# microcontroller.net
KiCad netlist of a schematic drawn in Altium Designer
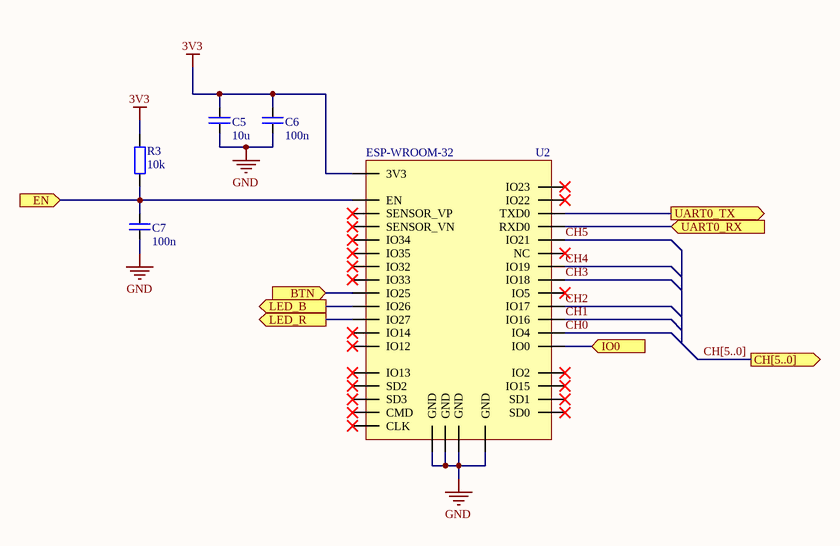
[diagram p0: microcontroller.SchDoc]

(export (version "E")
  (design (tool "Eeschema 10.0.6"))
  (components
    (comp (ref "C5")
      (value "10u")
      (footprint "capacitor_smd_0805")
      (description "TAIYO YUDEN TMK212BBJ106MGHT")
      (libsource (lib "generic") (part "Capacitor - non-polarised"))
    )
    (comp (ref "C6")
      (value "100n")
      (footprint "capacitor_smd_0603")
      (description "Vishay GA0603Y104KXAAC31G")
      (libsource (lib "generic") (part "Capacitor - non-polarised"))
    )
    (comp (ref "C7")
      (value "100n")
      (footprint "capacitor_smd_0603")
      (description "Vishay GA0603Y104KXAAC31G")
      (libsource (lib "generic") (part "Capacitor - non-polarised"))
    )
    (comp (ref "R3")
      (value "10k")
      (footprint "resisitor_smd_0603")
      (description "Vishay CRCW060310K0FKEI")
      (libsource (lib "generic") (part "Resistor"))
    )
    (comp (ref "U2")
      (value "ESP-WROOM-32")
      (footprint "ESP-WROOM-32_no_silk")
      (description "Espressif ESP-WROOM-32")
      (libsource (lib "integrated_circuits") (part "ESP-WROOM-32"))
    )
  )
  (nets
    (net (code "1") (name "/BTN") (class "Default")
      (node (ref "U2") (pin "10") (pinfunction "IO25_10") (pintype "passive"))
    )
    (net (code "2") (name "/CH0") (class "Default")
      (node (ref "U2") (pin "26") (pinfunction "IO4_26") (pintype "passive"))
    )
    (net (code "3") (name "/CH1") (class "Default")
      (node (ref "U2") (pin "27") (pinfunction "IO16_27") (pintype "passive"))
    )
    (net (code "4") (name "/CH2") (class "Default")
      (node (ref "U2") (pin "28") (pinfunction "IO17_28") (pintype "passive"))
    )
    (net (code "5") (name "/CH3") (class "Default")
      (node (ref "U2") (pin "30") (pinfunction "IO18_30") (pintype "passive"))
    )
    (net (code "6") (name "/CH4") (class "Default")
      (node (ref "U2") (pin "31") (pinfunction "IO19_31") (pintype "passive"))
    )
    (net (code "7") (name "/CH5") (class "Default")
      (node (ref "U2") (pin "33") (pinfunction "IO21_33") (pintype "passive"))
    )
    (net (code "9") (name "/EN") (class "Default")
      (node (ref "C7") (pin "1") (pintype "passive"))
      (node (ref "R3") (pin "2") (pintype "passive"))
      (node (ref "U2") (pin "3") (pinfunction "EN_3") (pintype "passive"))
    )
    (net (code "10") (name "/IO0") (class "Default")
      (node (ref "U2") (pin "25") (pinfunction "IO0_25") (pintype "passive"))
    )
    (net (code "11") (name "/LED_B") (class "Default")
      (node (ref "U2") (pin "11") (pinfunction "IO26_11") (pintype "passive"))
    )
    (net (code "12") (name "/LED_R") (class "Default")
      (node (ref "U2") (pin "12") (pinfunction "IO27_12") (pintype "passive"))
    )
    (net (code "13") (name "/UART0_RX") (class "Default")
      (node (ref "U2") (pin "34") (pinfunction "RXD0_34") (pintype "passive"))
    )
    (net (code "14") (name "/UART0_TX") (class "Default")
      (node (ref "U2") (pin "35") (pinfunction "TXD0_35") (pintype "passive"))
    )
    (net (code "15") (name "3V3") (class "Default")
      (node (ref "C5") (pin "1") (pintype "passive"))
      (node (ref "C6") (pin "1") (pintype "passive"))
      (node (ref "R3") (pin "1") (pintype "passive"))
      (node (ref "U2") (pin "2") (pinfunction "3V3_2") (pintype "passive"))
    )
    (net (code "16") (name "GND") (class "Default")
      (node (ref "C5") (pin "2") (pintype "passive"))
      (node (ref "C6") (pin "2") (pintype "passive"))
      (node (ref "C7") (pin "2") (pintype "passive"))
      (node (ref "U2") (pin "1") (pinfunction "GND_1") (pintype "passive"))
      (node (ref "U2") (pin "15") (pinfunction "GND_15") (pintype "passive"))
      (node (ref "U2") (pin "38") (pinfunction "GND_38") (pintype "passive"))
      (node (ref "U2") (pin "39") (pinfunction "GND_39") (pintype "passive"))
    )
    (net (code "17") (name "unconnected-(U2-CLK-Pad20)") (class "Default")
      (node (ref "U2") (pin "20") (pinfunction "CLK_20") (pintype "passive+no_connect"))
    )
    (net (code "18") (name "unconnected-(U2-CMD-Pad19)") (class "Default")
      (node (ref "U2") (pin "19") (pinfunction "CMD_19") (pintype "passive+no_connect"))
    )
    (net (code "19") (name "unconnected-(U2-IO2-Pad24)") (class "Default")
      (node (ref "U2") (pin "24") (pinfunction "IO2_24") (pintype "passive+no_connect"))
    )
    (net (code "20") (name "unconnected-(U2-IO5-Pad29)") (class "Default")
      (node (ref "U2") (pin "29") (pinfunction "IO5_29") (pintype "passive+no_connect"))
    )
    (net (code "21") (name "unconnected-(U2-IO12-Pad14)") (class "Default")
      (node (ref "U2") (pin "14") (pinfunction "IO12_14") (pintype "passive+no_connect"))
    )
    (net (code "22") (name "unconnected-(U2-IO13-Pad16)") (class "Default")
      (node (ref "U2") (pin "16") (pinfunction "IO13_16") (pintype "passive+no_connect"))
    )
    (net (code "23") (name "unconnected-(U2-IO14-Pad13)") (class "Default")
      (node (ref "U2") (pin "13") (pinfunction "IO14_13") (pintype "passive+no_connect"))
    )
    (net (code "24") (name "unconnected-(U2-IO15-Pad23)") (class "Default")
      (node (ref "U2") (pin "23") (pinfunction "IO15_23") (pintype "passive+no_connect"))
    )
    (net (code "25") (name "unconnected-(U2-IO22-Pad36)") (class "Default")
      (node (ref "U2") (pin "36") (pinfunction "IO22_36") (pintype "passive+no_connect"))
    )
    (net (code "26") (name "unconnected-(U2-IO23-Pad37)") (class "Default")
      (node (ref "U2") (pin "37") (pinfunction "IO23_37") (pintype "passive+no_connect"))
    )
    (net (code "27") (name "unconnected-(U2-IO32-Pad8)") (class "Default")
      (node (ref "U2") (pin "8") (pinfunction "IO32_8") (pintype "passive+no_connect"))
    )
    (net (code "28") (name "unconnected-(U2-IO33-Pad9)") (class "Default")
      (node (ref "U2") (pin "9") (pinfunction "IO33_9") (pintype "passive+no_connect"))
    )
    (net (code "29") (name "unconnected-(U2-IO34-Pad6)") (class "Default")
      (node (ref "U2") (pin "6") (pinfunction "IO34_6") (pintype "passive+no_connect"))
    )
    (net (code "30") (name "unconnected-(U2-IO35-Pad7)") (class "Default")
      (node (ref "U2") (pin "7") (pinfunction "IO35_7") (pintype "passive+no_connect"))
    )
    (net (code "31") (name "unconnected-(U2-NC-Pad32)") (class "Default")
      (node (ref "U2") (pin "32") (pinfunction "NC_32") (pintype "passive+no_connect"))
    )
    (net (code "32") (name "unconnected-(U2-SD0-Pad21)") (class "Default")
      (node (ref "U2") (pin "21") (pinfunction "SD0_21") (pintype "passive+no_connect"))
    )
    (net (code "33") (name "unconnected-(U2-SD1-Pad22)") (class "Default")
      (node (ref "U2") (pin "22") (pinfunction "SD1_22") (pintype "passive+no_connect"))
    )
    (net (code "34") (name "unconnected-(U2-SD2-Pad17)") (class "Default")
      (node (ref "U2") (pin "17") (pinfunction "SD2_17") (pintype "passive+no_connect"))
    )
    (net (code "35") (name "unconnected-(U2-SD3-Pad18)") (class "Default")
      (node (ref "U2") (pin "18") (pinfunction "SD3_18") (pintype "passive+no_connect"))
    )
    (net (code "36") (name "unconnected-(U2-SENSOR_VN-Pad5)") (class "Default")
      (node (ref "U2") (pin "5") (pinfunction "SENSOR_VN_5") (pintype "passive+no_connect"))
    )
    (net (code "37") (name "unconnected-(U2-SENSOR_VP-Pad4)") (class "Default")
      (node (ref "U2") (pin "4") (pinfunction "SENSOR_VP_4") (pintype "passive+no_connect"))
    )
  )
)
